# Supply_DAC.net
KiCad netlist of a schematic drawn in Altium Designer
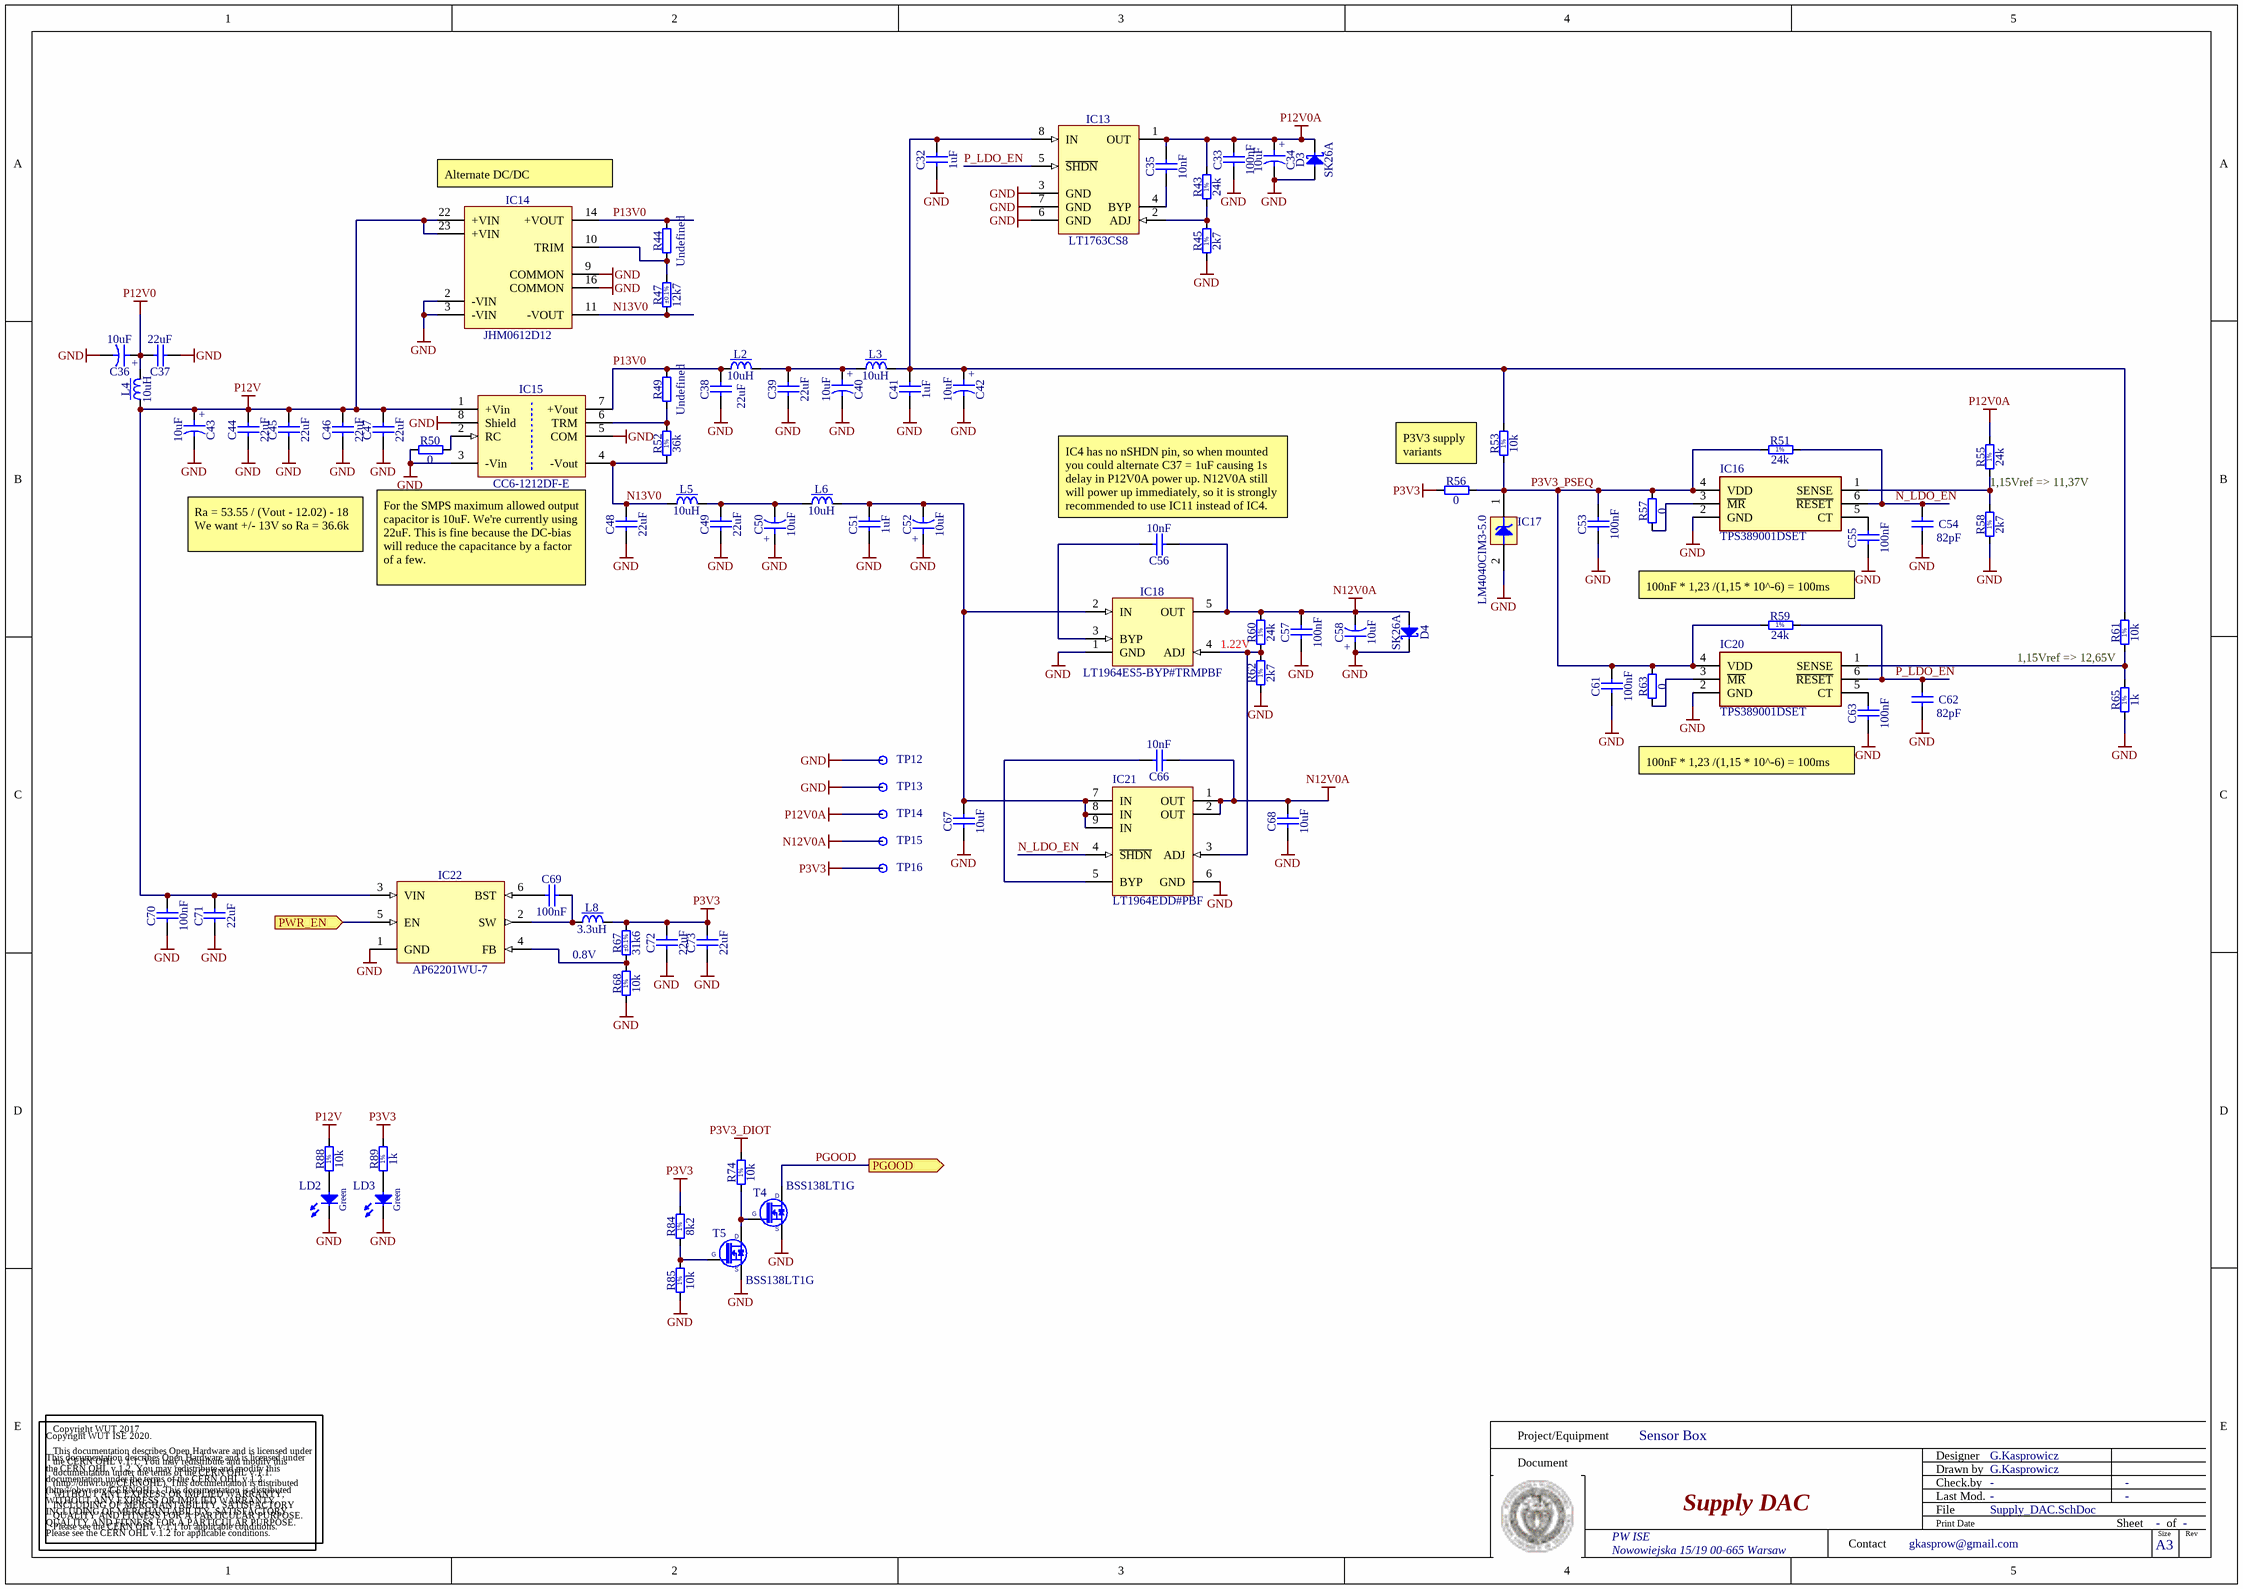
[diagram p0: Supply_DAC.SchDoc]

(export (version "E")
  (design (tool "Eeschema 10.0.6"))
  (components
    (comp (ref "C32")
      (value "1uF")
      (footprint "CAPC1608X87N")
      (description "Non-polarised capacitor")
      (fields
        (field (name "PART NUMBER") "CC0603_1UF_25V_10%_X7R")
        (field (name "VOLTAGE") "25V")
        (field (name "AUTHOR") "CERN DEM JLC")
      )
      (libsource (lib "Capacitors") (part "Capacitor - non polarized"))
    )
    (comp (ref "C33")
      (value "100nF")
      (footprint "CAPC1005X55N")
      (description "Non-polarised capacitor")
      (fields
        (field (name "PART NUMBER") "CC0402_100NF_16V_10%_X5R")
        (field (name "VOLTAGE") "16V")
        (field (name "AUTHOR") "CERN DEM JLC")
      )
      (libsource (lib "Capacitors") (part "Capacitor - non polarized"))
    )
    (comp (ref "C34")
      (value "10uF")
      (footprint "CAPMP3216X180N")
      (description "Polarised capacitor")
      (fields
        (field (name "PART NUMBER") "CTE3216-18_10UF_16V_20%_AVX_TCJ")
        (field (name "VOLTAGE") "16V")
        (field (name "AUTHOR") "CERN DEM JLC")
      )
      (libsource (lib "Capacitors") (part "Capacitor - polarized"))
    )
    (comp (ref "C35")
      (value "10nF")
      (footprint "CAPC1608X87N")
      (description "Non-polarised capacitor")
      (fields
        (field (name "PART NUMBER") "CC0603_10NF_50V_10%_X7R")
        (field (name "VOLTAGE") "50V")
        (field (name "AUTHOR") "CERN DEM JLC")
      )
      (libsource (lib "Capacitors") (part "Capacitor - non polarized"))
    )
    (comp (ref "C36")
      (value "10uF")
      (footprint "CAPMP3216X180N")
      (description "Polarised capacitor")
      (fields
        (field (name "PART NUMBER") "CTE3216-18_10UF_16V_20%_AVX_TCJ")
        (field (name "VOLTAGE") "16V")
        (field (name "AUTHOR") "CERN DEM JLC")
      )
      (libsource (lib "Capacitors") (part "Capacitor - polarized"))
    )
    (comp (ref "C37")
      (value "22uF")
      (footprint "CAPC2012X135N")
      (description "Non-polarised capacitor")
      (fields
        (field (name "PART NUMBER") "CC0805_22UF_16V_10%_X5R")
        (field (name "VOLTAGE") "16V")
        (field (name "AUTHOR") "CERN DEM JLC")
      )
      (libsource (lib "Capacitors") (part "Capacitor - non polarized"))
    )
    (comp (ref "C38")
      (value "22uF")
      (footprint "CAPC2012X135N")
      (description "Non-polarised capacitor")
      (fields
        (field (name "PART NUMBER") "CC0805_22UF_16V_10%_X5R")
        (field (name "VOLTAGE") "16V")
        (field (name "AUTHOR") "CERN DEM JLC")
      )
      (libsource (lib "Capacitors") (part "Capacitor - non polarized"))
    )
    (comp (ref "C39")
      (value "22uF")
      (footprint "CAPC2012X135N")
      (description "Non-polarised capacitor")
      (fields
        (field (name "PART NUMBER") "CC0805_22UF_16V_10%_X5R")
        (field (name "VOLTAGE") "16V")
        (field (name "AUTHOR") "CERN DEM JLC")
      )
      (libsource (lib "Capacitors") (part "Capacitor - non polarized"))
    )
    (comp (ref "C40")
      (value "10uF")
      (footprint "CAPMP3216X180N")
      (description "Polarised capacitor")
      (fields
        (field (name "PART NUMBER") "CTE3216-18_10UF_16V_20%_AVX_TCJ")
        (field (name "VOLTAGE") "16V")
        (field (name "AUTHOR") "CERN DEM JLC")
      )
      (libsource (lib "Capacitors") (part "Capacitor - polarized"))
    )
    (comp (ref "C41")
      (value "1uF")
      (footprint "CAPC1608X87N")
      (description "Non-polarised capacitor")
      (fields
        (field (name "PART NUMBER") "CC0603_1UF_25V_10%_X7R")
        (field (name "VOLTAGE") "25V")
        (field (name "AUTHOR") "CERN DEM JLC")
      )
      (libsource (lib "Capacitors") (part "Capacitor - non polarized"))
    )
    (comp (ref "C42")
      (value "10uF")
      (footprint "CAPMP3216X180N")
      (description "Polarised capacitor")
      (fields
        (field (name "PART NUMBER") "CTE3216-18_10UF_16V_20%_AVX_TCJ")
        (field (name "VOLTAGE") "16V")
        (field (name "AUTHOR") "CERN DEM JLC")
      )
      (libsource (lib "Capacitors") (part "Capacitor - polarized"))
    )
    (comp (ref "C43")
      (value "10uF")
      (footprint "CAPMP3216X180N")
      (description "Polarised capacitor")
      (fields
        (field (name "PART NUMBER") "CTE3216-18_10UF_16V_20%_AVX_TCJ")
        (field (name "VOLTAGE") "16V")
        (field (name "AUTHOR") "CERN DEM JLC")
      )
      (libsource (lib "Capacitors") (part "Capacitor - polarized"))
    )
    (comp (ref "C44")
      (value "22uF")
      (footprint "CAPC2012X135N")
      (description "Non-polarised capacitor")
      (fields
        (field (name "PART NUMBER") "CC0805_22UF_16V_10%_X5R")
        (field (name "VOLTAGE") "16V")
        (field (name "AUTHOR") "CERN DEM JLC")
      )
      (libsource (lib "Capacitors") (part "Capacitor - non polarized"))
    )
    (comp (ref "C45")
      (value "22uF")
      (footprint "CAPC2012X135N")
      (description "Non-polarised capacitor")
      (fields
        (field (name "PART NUMBER") "CC0805_22UF_16V_10%_X5R")
        (field (name "VOLTAGE") "16V")
        (field (name "AUTHOR") "CERN DEM JLC")
      )
      (libsource (lib "Capacitors") (part "Capacitor - non polarized"))
    )
    (comp (ref "C46")
      (value "22uF")
      (footprint "CAPC2012X135N")
      (description "Non-polarised capacitor")
      (fields
        (field (name "PART NUMBER") "CC0805_22UF_16V_10%_X5R")
        (field (name "VOLTAGE") "16V")
        (field (name "AUTHOR") "CERN DEM JLC")
      )
      (libsource (lib "Capacitors") (part "Capacitor - non polarized"))
    )
    (comp (ref "C47")
      (value "22uF")
      (footprint "CAPC2012X135N")
      (description "Non-polarised capacitor")
      (fields
        (field (name "PART NUMBER") "CC0805_22UF_16V_10%_X5R")
        (field (name "VOLTAGE") "16V")
        (field (name "AUTHOR") "CERN DEM JLC")
      )
      (libsource (lib "Capacitors") (part "Capacitor - non polarized"))
    )
    (comp (ref "C48")
      (value "22uF")
      (footprint "CAPC2012X135N")
      (description "Non-polarised capacitor")
      (fields
        (field (name "PART NUMBER") "CC0805_22UF_16V_10%_X5R")
        (field (name "VOLTAGE") "16V")
        (field (name "AUTHOR") "CERN DEM JLC")
      )
      (libsource (lib "Capacitors") (part "Capacitor - non polarized"))
    )
    (comp (ref "C49")
      (value "22uF")
      (footprint "CAPC2012X135N")
      (description "Non-polarised capacitor")
      (fields
        (field (name "PART NUMBER") "CC0805_22UF_16V_10%_X5R")
        (field (name "VOLTAGE") "16V")
        (field (name "AUTHOR") "CERN DEM JLC")
      )
      (libsource (lib "Capacitors") (part "Capacitor - non polarized"))
    )
    (comp (ref "C50")
      (value "10uF")
      (footprint "CAPMP3216X180N")
      (description "Polarised capacitor")
      (fields
        (field (name "PART NUMBER") "CTE3216-18_10UF_16V_20%_AVX_TCJ")
        (field (name "VOLTAGE") "16V")
        (field (name "AUTHOR") "CERN DEM JLC")
      )
      (libsource (lib "Capacitors") (part "Capacitor - polarized"))
    )
    (comp (ref "C51")
      (value "1uF")
      (footprint "CAPC1608X87N")
      (description "Non-polarised capacitor")
      (fields
        (field (name "PART NUMBER") "CC0603_1UF_25V_10%_X7R")
        (field (name "VOLTAGE") "25V")
        (field (name "AUTHOR") "CERN DEM JLC")
      )
      (libsource (lib "Capacitors") (part "Capacitor - non polarized"))
    )
    (comp (ref "C52")
      (value "10uF")
      (footprint "CAPMP3216X180N")
      (description "Polarised capacitor")
      (fields
        (field (name "PART NUMBER") "CTE3216-18_10UF_16V_20%_AVX_TCJ")
        (field (name "VOLTAGE") "16V")
        (field (name "AUTHOR") "CERN DEM JLC")
      )
      (libsource (lib "Capacitors") (part "Capacitor - polarized"))
    )
    (comp (ref "C53")
      (value "100nF")
      (footprint "CAPC1005X55N")
      (description "Non-polarised capacitor")
      (fields
        (field (name "PART NUMBER") "CC0402_100NF_16V_10%_X5R")
        (field (name "VOLTAGE") "16V")
        (field (name "AUTHOR") "CERN DEM JLC")
      )
      (libsource (lib "Capacitors") (part "Capacitor - non polarized"))
    )
    (comp (ref "C54")
      (value "82pF")
      (footprint "CAPC1608X87N")
      (description "Non-polarised capacitor")
      (fields
        (field (name "PART NUMBER") "CC0603_82PF_50V_5%_NP0")
        (field (name "VOLTAGE") "50V")
        (field (name "AUTHOR") "CERN DEM JLC")
      )
      (libsource (lib "Capacitors") (part "Capacitor - non polarized"))
    )
    (comp (ref "C55")
      (value "100nF")
      (footprint "CAPC1005X55N")
      (description "Non-polarised capacitor")
      (fields
        (field (name "PART NUMBER") "CC0402_100NF_16V_10%_X5R")
        (field (name "VOLTAGE") "16V")
        (field (name "AUTHOR") "CERN DEM JLC")
      )
      (libsource (lib "Capacitors") (part "Capacitor - non polarized"))
    )
    (comp (ref "C56")
      (value "10nF")
      (footprint "CAPC1608X87N")
      (description "Non-polarised capacitor")
      (fields
        (field (name "PART NUMBER") "CC0603_10NF_50V_10%_X7R")
        (field (name "VOLTAGE") "50V")
        (field (name "AUTHOR") "CERN DEM JLC")
      )
      (libsource (lib "Capacitors") (part "Capacitor - non polarized"))
    )
    (comp (ref "C57")
      (value "100nF")
      (footprint "CAPC1005X55N")
      (description "Non-polarised capacitor")
      (fields
        (field (name "PART NUMBER") "CC0402_100NF_16V_10%_X5R")
        (field (name "VOLTAGE") "16V")
        (field (name "AUTHOR") "CERN DEM JLC")
      )
      (libsource (lib "Capacitors") (part "Capacitor - non polarized"))
    )
    (comp (ref "C58")
      (value "10uF")
      (footprint "CAPMP3216X180N")
      (description "Polarised capacitor")
      (fields
        (field (name "PART NUMBER") "CTE3216-18_10UF_16V_20%_AVX_TCJ")
        (field (name "VOLTAGE") "16V")
        (field (name "AUTHOR") "CERN DEM JLC")
      )
      (libsource (lib "Capacitors") (part "Capacitor - polarized"))
    )
    (comp (ref "C61")
      (value "100nF")
      (footprint "CAPC1005X55N")
      (description "Non-polarised capacitor")
      (fields
        (field (name "PART NUMBER") "CC0402_100NF_16V_10%_X5R")
        (field (name "VOLTAGE") "16V")
        (field (name "AUTHOR") "CERN DEM JLC")
      )
      (libsource (lib "Capacitors") (part "Capacitor - non polarized"))
    )
    (comp (ref "C62")
      (value "82pF")
      (footprint "CAPC1608X87N")
      (description "Non-polarised capacitor")
      (fields
        (field (name "PART NUMBER") "CC0603_82PF_50V_5%_NP0")
        (field (name "VOLTAGE") "50V")
        (field (name "AUTHOR") "CERN DEM JLC")
      )
      (libsource (lib "Capacitors") (part "Capacitor - non polarized"))
    )
    (comp (ref "C63")
      (value "100nF")
      (footprint "CAPC1005X55N")
      (description "Non-polarised capacitor")
      (fields
        (field (name "PART NUMBER") "CC0402_100NF_16V_10%_X5R")
        (field (name "VOLTAGE") "16V")
        (field (name "AUTHOR") "CERN DEM JLC")
      )
      (libsource (lib "Capacitors") (part "Capacitor - non polarized"))
    )
    (comp (ref "C66")
      (value "10nF")
      (footprint "CAPC1608X87N")
      (description "Non-polarised capacitor")
      (fields
        (field (name "PART NUMBER") "CC0603_10NF_50V_10%_X7R")
        (field (name "VOLTAGE") "50V")
        (field (name "AUTHOR") "CERN DEM JLC")
      )
      (libsource (lib "Capacitors") (part "Capacitor - non polarized"))
    )
    (comp (ref "C67")
      (value "10uF")
      (footprint "CAPC1608X80N")
      (description "Non-polarised capacitor")
      (fields
        (field (name "PART NUMBER") "CC0603_10UF_16V_20%_X5R")
        (field (name "VOLTAGE") "16V")
        (field (name "AUTHOR") "CERN DEM MR")
      )
      (libsource (lib "Capacitors") (part "Capacitor - non polarized"))
    )
    (comp (ref "C68")
      (value "10uF")
      (footprint "CAPC1608X80N")
      (description "Non-polarised capacitor")
      (fields
        (field (name "PART NUMBER") "CC0603_10UF_16V_20%_X5R")
        (field (name "VOLTAGE") "16V")
        (field (name "AUTHOR") "CERN DEM MR")
      )
      (libsource (lib "Capacitors") (part "Capacitor - non polarized"))
    )
    (comp (ref "C69")
      (value "100nF")
      (footprint "CAPC1005X55N")
      (description "Non-polarised capacitor")
      (fields
        (field (name "PART NUMBER") "CC0402_100NF_16V_10%_X5R")
        (field (name "VOLTAGE") "16V")
        (field (name "AUTHOR") "CERN DEM JLC")
      )
      (libsource (lib "Capacitors") (part "Capacitor - non polarized"))
    )
    (comp (ref "C70")
      (value "100nF")
      (footprint "CAPC1005X55N")
      (description "Non-polarised capacitor")
      (fields
        (field (name "PART NUMBER") "CC0402_100NF_16V_10%_X5R")
        (field (name "VOLTAGE") "16V")
        (field (name "AUTHOR") "CERN DEM JLC")
      )
      (libsource (lib "Capacitors") (part "Capacitor - non polarized"))
    )
    (comp (ref "C71")
      (value "22uF")
      (footprint "CAPC2012X135N")
      (description "Non-polarised capacitor")
      (fields
        (field (name "PART NUMBER") "CC0805_22UF_16V_10%_X5R")
        (field (name "VOLTAGE") "16V")
        (field (name "AUTHOR") "CERN DEM JLC")
      )
      (libsource (lib "Capacitors") (part "Capacitor - non polarized"))
    )
    (comp (ref "C72")
      (value "22uF")
      (footprint "CAPC2012X135N")
      (description "Non-polarised capacitor")
      (fields
        (field (name "PART NUMBER") "CC0805_22UF_16V_10%_X5R")
        (field (name "VOLTAGE") "16V")
        (field (name "AUTHOR") "CERN DEM JLC")
      )
      (libsource (lib "Capacitors") (part "Capacitor - non polarized"))
    )
    (comp (ref "C73")
      (value "22uF")
      (footprint "CAPC2012X135N")
      (description "Non-polarised capacitor")
      (fields
        (field (name "PART NUMBER") "CC0805_22UF_16V_10%_X5R")
        (field (name "VOLTAGE") "16V")
        (field (name "AUTHOR") "CERN DEM JLC")
      )
      (libsource (lib "Capacitors") (part "Capacitor - non polarized"))
    )
    (comp (ref "D3")
      (value "SK26A")
      (footprint "DIOM5126X265N")
      (description "Schottky Diode")
      (fields
        (field (name "VOLTAGE") "60V")
        (field (name "POWER") "2A")
        (field (name "AUTHOR") "CERN DEM JMW")
      )
      (libsource (lib "ICs And Semiconductors") (part "Diode Schottky"))
    )
    (comp (ref "D4")
      (value "SK26A")
      (footprint "DIOM5126X265N")
      (description "Schottky Diode")
      (fields
        (field (name "VOLTAGE") "60V")
        (field (name "POWER") "2A")
        (field (name "AUTHOR") "CERN DEM JMW")
      )
      (libsource (lib "ICs And Semiconductors") (part "Diode Schottky"))
    )
    (comp (ref "IC13")
      (value "LT1763CS8")
      (footprint "SOIC127P600X175-8N")
      (description "1.22V to 20V 500mA, Low Noise, LDO Adjustable Micropower Regulator")
      (fields (field (name "MANUFACTURER") "LINEAR TECHNOLOGY") (field (name "AUTHOR") "CERN DEM JLC"))
      (libsource (lib "ICs And Semiconductors") (part "LT1763xS8"))
    )
    (comp (ref "IC14")
      (value "JHM0612D12")
      (footprint "DCDC_XPPOWER_JHM0X")
      (description "9-72VDC to 3.3-15VDC, Iout (max) 500mA, DC-DC Converter")
      (fields (field (name "MANUFACTURER") "XP POWER") (field (name "AUTHOR") "CERN DEM HF"))
      (libsource (lib "ICs And Semiconductors") (part "DCDC_XPPOWER_JHM0xxxD"))
    )
    (comp (ref "IC15")
      (value "CC6-1212DF-E")
      (footprint "CC6-1212DF-E")
      (description "CONV DC/DC 6W DUAL 12V +-12V PCB")
      (fields (field (name "MANUFACTURER") "TDK-Lambda Americas Inc.") (field (name "AUTHOR") "GK"))
      (libsource (lib "Regulators_SMPS") (part "DC/DC_CC6-1212DF-E"))
    )
    (comp (ref "IC16")
      (value "TPS389001DSET")
      (footprint "TPS610985DSET")
      (description "Supervisory Circuits Low-quiescent current 1% accuracy supervisor with programmable delay")
      (fields (field (name "MOUSER PART NUMBER") "595-TPS389001DSET"))
      (libsource (lib "Integrated_Library_LOADER") (part "TPS389001DSET"))
    )
    (comp (ref "IC17")
      (value "LM4040CIM3-5.0")
      (footprint "SOT95P237X112-3N")
      (description "Integrated Circuit")
      (fields (field (name "MOUSER PART NUMBER") "926-LM4040CIM3-50"))
      (libsource (lib "Integrated_Library_LOADER") (part "LM4040CIM3-5.0"))
    )
    (comp (ref "IC18")
      (value "LT1964ES5-BYP#TRMPBF")
      (footprint "SOT95P280X100-5N")
      (description "200mA, Low Noise, Low Dropout Negative Micropower Regulator")
      (fields (field (name "MANUFACTURER") "LINEAR TECHNOLOGY") (field (name "AUTHOR") "CERN DEM MR"))
      (libsource (lib "ICs And Semiconductors") (part "LT1964-BYP"))
    )
    (comp (ref "IC20")
      (value "TPS389001DSET")
      (footprint "TPS610985DSET")
      (description "Supervisory Circuits Low-quiescent current 1% accuracy supervisor with programmable delay")
      (fields (field (name "MOUSER PART NUMBER") "595-TPS389001DSET"))
      (libsource (lib "Integrated_Library_LOADER") (part "TPS389001DSET"))
    )
    (comp (ref "IC21")
      (value "LT1964EDD#PBF")
      (footprint "LT-DD-8_V")
      (fields (field (name "MANUFACTURER") "Linear Technology"))
      (libsource (lib "Altium Content Vault") (part "LT-LT1964-DD-8"))
    )
    (comp (ref "IC22")
      (value "AP62201WU-7")
      (footprint "SOT95P280X100-6N")
      (description "4.2V TO 18V INPUT, 2A LOW IQ SYNCHRONOUS BUCK CONVERTER")
      (fields
        (field (name "MANUFACTURER") "DIODES INCORPORATED")
        (field (name "MANUFACTURER PART NUMBER") "AP62201WU")
        (field (name "AUTHOR") "CERN DEM HF")
      )
      (libsource (lib "ICs And Semiconductors") (part "AP62201WU"))
    )
    (comp (ref "L2")
      (value "10uH")
      (footprint "IND_MURATA-PS_8400")
      (description "Inductor With Core")
      (fields
        (field (name "PART NUMBER") "IND_10UH_10%_MURATA-PS_8400")
        (field (name "POWER") "950mA")
        (field (name "AUTHOR") "CERN DEM JLC")
      )
      (libsource (lib "Inductors & Transformers") (part "Inductor With Magnetic core"))
    )
    (comp (ref "L3")
      (value "10uH")
      (footprint "IND_MURATA-PS_8400")
      (description "Inductor With Core")
      (fields
        (field (name "PART NUMBER") "IND_10UH_10%_MURATA-PS_8400")
        (field (name "POWER") "950mA")
        (field (name "AUTHOR") "CERN DEM JLC")
      )
      (libsource (lib "Inductors & Transformers") (part "Inductor With Magnetic core"))
    )
    (comp (ref "L4")
      (value "10uH")
      (footprint "IND_MURATA-PS_8400")
      (description "Inductor With Core")
      (fields
        (field (name "PART NUMBER") "IND_10UH_10%_MURATA-PS_8400")
        (field (name "POWER") "950mA")
        (field (name "AUTHOR") "CERN DEM JLC")
      )
      (libsource (lib "") (part "Inductor With Magnetic core_1"))
    )
    (comp (ref "L5")
      (value "10uH")
      (footprint "IND_MURATA-PS_8400")
      (description "Inductor With Core")
      (fields
        (field (name "PART NUMBER") "IND_10UH_10%_MURATA-PS_8400")
        (field (name "POWER") "950mA")
        (field (name "AUTHOR") "CERN DEM JLC")
      )
      (libsource (lib "Inductors & Transformers") (part "Inductor With Magnetic core"))
    )
    (comp (ref "L6")
      (value "10uH")
      (footprint "IND_MURATA-PS_8400")
      (description "Inductor With Core")
      (fields
        (field (name "PART NUMBER") "IND_10UH_10%_MURATA-PS_8400")
        (field (name "POWER") "950mA")
        (field (name "AUTHOR") "CERN DEM JLC")
      )
      (libsource (lib "Inductors & Transformers") (part "Inductor With Magnetic core"))
    )
    (comp (ref "L8")
      (value "3.3uH")
      (footprint "IND_WURTH_WE-TPC_4828")
      (description "Inductor With Core")
      (fields
        (field (name "PART NUMBER") "IND_3.3UH_30%_WURTH_WE-TPC_744043003")
        (field (name "POWER") "2.15A")
        (field (name "AUTHOR") "CERN DEM JLC")
      )
      (libsource (lib "Inductors & Transformers") (part "Inductor With Magnetic core"))
    )
    (comp (ref "LD2")
      (value "Green")
      (footprint "LED_KINGBRIGHT_KPH-1608CGCK")
      (description "LED Green 1C 2A")
      (fields
        (field (name "MANUFACTURER PART NUMBER") "KPH-1608CGCK")
        (field (name "PART NUMBER") "LED_KINGBRIGHT_KPH-1608CGCK")
        (field (name "AUTHOR") "CERN DEM JLC")
      )
      (libsource (lib "ICs And Semiconductors") (part "LED Green 1C 2A"))
    )
    (comp (ref "LD3")
      (value "Green")
      (footprint "LED_KINGBRIGHT_KPH-1608CGCK")
      (description "LED Green 1C 2A")
      (fields
        (field (name "MANUFACTURER PART NUMBER") "KPH-1608CGCK")
        (field (name "PART NUMBER") "LED_KINGBRIGHT_KPH-1608CGCK")
        (field (name "AUTHOR") "CERN DEM JLC")
      )
      (libsource (lib "ICs And Semiconductors") (part "LED Green 1C 2A"))
    )
    (comp (ref "R43")
      (value "24k")
      (footprint "RESC1608X55N")
      (description "Resistor - 1%")
      (fields
        (field (name "PART NUMBER") "R0603_24K_1%_0.1W_100PPM")
        (field (name "POWER") "0.1W")
        (field (name "AUTHOR") "CERN DEM JLC")
      )
      (libsource (lib "Resistors") (part "Resistor - 1%"))
    )
    (comp (ref "R44")
      (value "Undefined")
      (footprint "RESC1608X55N")
      (description "Resistor")
      (fields (field (name "PART NUMBER") "R0603_NO-VALUE") (field (name "AUTHOR") "CERN DEM JLC"))
      (libsource (lib "Resistors") (part "Resistor"))
    )
    (comp (ref "R45")
      (value "2k7")
      (footprint "RESC1608X55N")
      (description "Resistor - 1%")
      (fields
        (field (name "PART NUMBER") "R0603_2K7_1%_0.1W_100PPM")
        (field (name "POWER") "0.1W")
        (field (name "AUTHOR") "CERN DEM JLC")
      )
      (libsource (lib "Resistors") (part "Resistor - 1%"))
    )
    (comp (ref "R47")
      (value "12k7")
      (footprint "RESC1608X55N")
      (description "Resistor - 0.1%")
      (fields
        (field (name "TOLERANCE") "±0.1%")
        (field (name "PART NUMBER") "R0603_12K7_0.1%_0.063W_10PPM")
        (field (name "POWER") "0.063W")
        (field (name "AUTHOR") "CERN DEM JLC")
      )
      (libsource (lib "Resistors") (part "Resistor - 0.1%"))
    )
    (comp (ref "R49")
      (value "Undefined")
      (footprint "RESC1608X55N")
      (description "Resistor")
      (fields (field (name "PART NUMBER") "R0603_NO-VALUE") (field (name "AUTHOR") "CERN DEM JLC"))
      (libsource (lib "Resistors") (part "Resistor"))
    )
    (comp (ref "R50")
      (value "0")
      (footprint "RESC1005X40N")
      (description "Resistor")
      (fields
        (field (name "PART NUMBER") "R0402_0R_JUMPER")
        (field (name "MANUFACTURER") "GENERIC")
        (field (name "AUTHOR") "CERN DEM JLC")
      )
      (libsource (lib "Resistors") (part "Resistor"))
    )
    (comp (ref "R51")
      (value "24k")
      (footprint "RESC1608X55N")
      (description "Resistor - 1%")
      (fields
        (field (name "PART NUMBER") "R0603_24K_1%_0.1W_100PPM")
        (field (name "POWER") "0.1W")
        (field (name "AUTHOR") "CERN DEM JLC")
      )
      (libsource (lib "Resistors") (part "Resistor - 1%"))
    )
    (comp (ref "R52")
      (value "36k")
      (footprint "RESC1608X55N")
      (description "Resistor - 1%")
      (fields
        (field (name "PART NUMBER") "R0603_36K_1%_0.1W_100PPM")
        (field (name "POWER") "0.1W")
        (field (name "AUTHOR") "CERN DEM JLC")
      )
      (libsource (lib "Resistors") (part "Resistor - 1%"))
    )
    (comp (ref "R53")
      (value "10k")
      (footprint "RESC1005X40N")
      (description "Resistor - 1%")
      (fields
        (field (name "PART NUMBER") "R0402_10K_1%_0.0625W_100PPM")
        (field (name "POWER") "0.0625W")
        (field (name "AUTHOR") "CERN DEM JLC")
      )
      (libsource (lib "Resistors") (part "Resistor - 1%"))
    )
    (comp (ref "R55")
      (value "24k")
      (footprint "RESC1608X55N")
      (description "Resistor - 1%")
      (fields
        (field (name "PART NUMBER") "R0603_24K_1%_0.1W_100PPM")
        (field (name "POWER") "0.1W")
        (field (name "AUTHOR") "CERN DEM JLC")
      )
      (libsource (lib "Resistors") (part "Resistor - 1%"))
    )
    (comp (ref "R56")
      (value "0")
      (footprint "RESC1005X40N")
      (description "Resistor")
      (fields
        (field (name "PART NUMBER") "R0402_0R_JUMPER")
        (field (name "MANUFACTURER") "GENERIC")
        (field (name "AUTHOR") "CERN DEM JLC")
      )
      (libsource (lib "Resistors") (part "Resistor"))
    )
    (comp (ref "R57")
      (value "0")
      (footprint "RESC1005X40N")
      (description "Resistor")
      (fields
        (field (name "PART NUMBER") "R0402_0R_JUMPER")
        (field (name "MANUFACTURER") "GENERIC")
        (field (name "AUTHOR") "CERN DEM JLC")
      )
      (libsource (lib "Resistors") (part "Resistor"))
    )
    (comp (ref "R58")
      (value "2k7")
      (footprint "RESC1608X55N")
      (description "Resistor - 1%")
      (fields
        (field (name "PART NUMBER") "R0603_2K7_1%_0.1W_100PPM")
        (field (name "POWER") "0.1W")
        (field (name "AUTHOR") "CERN DEM JLC")
      )
      (libsource (lib "Resistors") (part "Resistor - 1%"))
    )
    (comp (ref "R59")
      (value "24k")
      (footprint "RESC1608X55N")
      (description "Resistor - 1%")
      (fields
        (field (name "PART NUMBER") "R0603_24K_1%_0.1W_100PPM")
        (field (name "POWER") "0.1W")
        (field (name "AUTHOR") "CERN DEM JLC")
      )
      (libsource (lib "Resistors") (part "Resistor - 1%"))
    )
    (comp (ref "R60")
      (value "24k")
      (footprint "RESC1608X55N")
      (description "Resistor - 1%")
      (fields
        (field (name "PART NUMBER") "R0603_24K_1%_0.1W_100PPM")
        (field (name "POWER") "0.1W")
        (field (name "AUTHOR") "CERN DEM JLC")
      )
      (libsource (lib "Resistors") (part "Resistor - 1%"))
    )
    (comp (ref "R61")
      (value "10k")
      (footprint "RESC1005X40N")
      (description "Resistor - 1%")
      (fields
        (field (name "PART NUMBER") "R0402_10K_1%_0.0625W_100PPM")
        (field (name "POWER") "0.0625W")
        (field (name "AUTHOR") "CERN DEM JLC")
      )
      (libsource (lib "Resistors") (part "Resistor - 1%"))
    )
    (comp (ref "R62")
      (value "2k7")
      (footprint "RESC1608X55N")
      (description "Resistor - 1%")
      (fields
        (field (name "PART NUMBER") "R0603_2K7_1%_0.1W_100PPM")
        (field (name "POWER") "0.1W")
        (field (name "AUTHOR") "CERN DEM JLC")
      )
      (libsource (lib "Resistors") (part "Resistor - 1%"))
    )
    (comp (ref "R63")
      (value "0")
      (footprint "RESC1005X40N")
      (description "Resistor")
      (fields
        (field (name "PART NUMBER") "R0402_0R_JUMPER")
        (field (name "MANUFACTURER") "GENERIC")
        (field (name "AUTHOR") "CERN DEM JLC")
      )
      (libsource (lib "Resistors") (part "Resistor"))
    )
    (comp (ref "R65")
      (value "1k")
      (footprint "RESC1608X55N")
      (description "Resistor - 1%")
      (fields
        (field (name "PART NUMBER") "R0603_1K_1%_0.1W_100PPM")
        (field (name "POWER") "0.1W")
        (field (name "AUTHOR") "CERN DEM JLC")
      )
      (libsource (lib "Resistors") (part "Resistor - 1%"))
    )
    (comp (ref "R67")
      (value "31k6")
      (footprint "RESC1005X35N")
      (description "Resistor - 0.1%")
      (fields
        (field (name "TOLERANCE") "±0.1%")
        (field (name "PART NUMBER") "R0402_31K6_0.1%_0.063W_25PPM_YAGEO_RT")
        (field (name "POWER") "0.063W")
        (field (name "AUTHOR") "CERN DEM BC")
      )
      (libsource (lib "Resistors") (part "Resistor - 0.1%"))
    )
    (comp (ref "R68")
      (value "10k")
      (footprint "RESC1005X40N")
      (description "Resistor - 1%")
      (fields
        (field (name "PART NUMBER") "R0402_10K_1%_0.0625W_100PPM")
        (field (name "POWER") "0.0625W")
        (field (name "AUTHOR") "CERN DEM JLC")
      )
      (libsource (lib "Resistors") (part "Resistor - 1%"))
    )
    (comp (ref "R74")
      (value "10k")
      (footprint "RESC1005X40N")
      (description "Resistor - 1%")
      (fields
        (field (name "PART NUMBER") "R0402_10K_1%_0.0625W_100PPM")
        (field (name "POWER") "0.0625W")
        (field (name "AUTHOR") "CERN DEM JLC")
      )
      (libsource (lib "Resistors") (part "Resistor - 1%"))
    )
    (comp (ref "R84")
      (value "8k2")
      (footprint "RESC1005X40N")
      (description "Resistor - 1%")
      (fields
        (field (name "PART NUMBER") "R0402_8K2_1%_0.0625W_100PPM")
        (field (name "POWER") "0.0625W")
        (field (name "AUTHOR") "CERN DEM JLC")
      )
      (libsource (lib "Resistors") (part "Resistor - 1%"))
    )
    (comp (ref "R85")
      (value "10k")
      (footprint "RESC1005X40N")
      (description "Resistor - 1%")
      (fields
        (field (name "PART NUMBER") "R0402_10K_1%_0.0625W_100PPM")
        (field (name "POWER") "0.0625W")
        (field (name "AUTHOR") "CERN DEM JLC")
      )
      (libsource (lib "Resistors") (part "Resistor - 1%"))
    )
    (comp (ref "R88")
      (value "10k")
      (footprint "RESC1005X40N")
      (description "Resistor - 1%")
      (fields
        (field (name "PART NUMBER") "R0402_10K_1%_0.0625W_100PPM")
        (field (name "POWER") "0.0625W")
        (field (name "AUTHOR") "CERN DEM JLC")
      )
      (libsource (lib "Resistors") (part "Resistor - 1%"))
    )
    (comp (ref "R89")
      (value "1k")
      (footprint "RESC1005X40N")
      (description "Resistor - 1%")
      (fields
        (field (name "PART NUMBER") "R0402_1K_1%_0.0625W_100PPM")
        (field (name "POWER") "0.0625W")
        (field (name "AUTHOR") "CERN DEM JLC")
      )
      (libsource (lib "Resistors") (part "Resistor - 1%"))
    )
    (comp (ref "T4")
      (value "BSS138LT1G")
      (footprint "SOT95P240X110-3N")
      (description "N-CHANNEL MOSFET WITH DIODE")
      (fields (field (name "MANUFACTURER") "ON SEMICONDUCTOR") (field (name "AUTHOR") "CERN DEM JLC"))
      (libsource (lib "ICs And Semiconductors") (part "N-MOSFET-D 1G 2S 3D"))
    )
    (comp (ref "T5")
      (value "BSS138LT1G")
      (footprint "SOT95P240X110-3N")
      (description "N-CHANNEL MOSFET WITH DIODE")
      (fields (field (name "MANUFACTURER") "ON SEMICONDUCTOR") (field (name "AUTHOR") "CERN DEM JLC"))
      (libsource (lib "ICs And Semiconductors") (part "N-MOSFET-D 1G 2S 3D"))
    )
    (comp (ref "TP12")
      (value "Test Point")
      (footprint "TPS127")
      (fields (field (name "PART NUMBER") "SMD_PAD_1.27X1.27MM") (field (name "AUTHOR") "CERN DEM JLC"))
      (libsource (lib "Eletro-mechanical") (part "Test Point"))
    )
    (comp (ref "TP13")
      (value "Test Point")
      (footprint "TPS127")
      (fields (field (name "PART NUMBER") "SMD_PAD_1.27X1.27MM") (field (name "AUTHOR") "CERN DEM JLC"))
      (libsource (lib "Eletro-mechanical") (part "Test Point"))
    )
    (comp (ref "TP14")
      (value "Test Point")
      (footprint "TPS127")
      (fields (field (name "PART NUMBER") "SMD_PAD_1.27X1.27MM") (field (name "AUTHOR") "CERN DEM JLC"))
      (libsource (lib "Eletro-mechanical") (part "Test Point"))
    )
    (comp (ref "TP15")
      (value "Test Point")
      (footprint "TPS127")
      (fields (field (name "PART NUMBER") "SMD_PAD_1.27X1.27MM") (field (name "AUTHOR") "CERN DEM JLC"))
      (libsource (lib "Eletro-mechanical") (part "Test Point"))
    )
    (comp (ref "TP16")
      (value "Test Point")
      (footprint "TPS127")
      (fields (field (name "PART NUMBER") "SMD_PAD_1.27X1.27MM") (field (name "AUTHOR") "CERN DEM JLC"))
      (libsource (lib "Eletro-mechanical") (part "Test Point"))
    )
  )
  (nets
    (net (code "1") (name "/N13V0") (class "Default")
      (node (ref "C48") (pin "2") (pinfunction "2_2") (pintype "passive"))
      (node (ref "IC14") (pin "11") (pinfunction "-VOUT_11") (pintype "power_in"))
      (node (ref "IC15") (pin "4") (pinfunction "-Vout_4") (pintype "power_in"))
      (node (ref "L5") (pin "1") (pinfunction "1_1") (pintype "passive"))
      (node (ref "R47") (pin "1") (pinfunction "1_1") (pintype "passive"))
      (node (ref "R52") (pin "1") (pinfunction "1_1") (pintype "passive"))
    )
    (net (code "2") (name "/N_LDO_EN") (class "Default")
      (node (ref "C54") (pin "2") (pinfunction "2_2") (pintype "passive"))
      (node (ref "IC16") (pin "6") (pinfunction "~{RESET}_6") (pintype "passive"))
      (node (ref "IC21") (pin "4") (pinfunction "~{SHDN}_4") (pintype "input"))
      (node (ref "R51") (pin "2") (pinfunction "2_2") (pintype "passive"))
    )
    (net (code "3") (name "/P3V3_PSEQ") (class "Default")
      (node (ref "C53") (pin "2") (pinfunction "2_2") (pintype "passive"))
      (node (ref "C61") (pin "2") (pinfunction "2_2") (pintype "passive"))
      (node (ref "IC16") (pin "4") (pinfunction "VDD_4") (pintype "passive"))
      (node (ref "IC17") (pin "1") (pinfunction "C_1") (pintype "passive"))
      (node (ref "IC20") (pin "4") (pinfunction "VDD_4") (pintype "passive"))
      (node (ref "R51") (pin "1") (pinfunction "1_1") (pintype "passive"))
      (node (ref "R53") (pin "1") (pinfunction "1_1") (pintype "passive"))
      (node (ref "R56") (pin "2") (pinfunction "2_2") (pintype "passive"))
      (node (ref "R57") (pin "2") (pinfunction "2_2") (pintype "passive"))
      (node (ref "R59") (pin "1") (pinfunction "1_1") (pintype "passive"))
      (node (ref "R63") (pin "2") (pinfunction "2_2") (pintype "passive"))
    )
    (net (code "4") (name "/P13V0") (class "Default")
      (node (ref "C38") (pin "2") (pinfunction "2_2") (pintype "passive"))
      (node (ref "IC14") (pin "14") (pinfunction "+VOUT_14") (pintype "power_in"))
      (node (ref "IC15") (pin "7") (pinfunction "+Vout_7") (pintype "power_in"))
      (node (ref "L2") (pin "1") (pinfunction "1_1") (pintype "passive"))
      (node (ref "R44") (pin "2") (pinfunction "2_2") (pintype "passive"))
      (node (ref "R49") (pin "2") (pinfunction "2_2") (pintype "passive"))
    )
    (net (code "5") (name "/PGOOD") (class "Default")
      (node (ref "T4") (pin "3") (pinfunction "D_3") (pintype "passive"))
    )
    (net (code "6") (name "/PWR_EN") (class "Default")
      (node (ref "IC22") (pin "5") (pinfunction "EN_5") (pintype "input"))
    )
    (net (code "7") (name "/P_LDO_EN") (class "Default")
      (node (ref "C62") (pin "2") (pinfunction "2_2") (pintype "passive"))
      (node (ref "IC13") (pin "5") (pinfunction "~{SHDN}_5") (pintype "input"))
      (node (ref "IC20") (pin "6") (pinfunction "~{RESET}_6") (pintype "passive"))
      (node (ref "R59") (pin "2") (pinfunction "2_2") (pintype "passive"))
    )
    (net (code "8") (name "GND") (class "Default")
      (node (ref "C32") (pin "1") (pinfunction "1_1") (pintype "passive"))
      (node (ref "C33") (pin "1") (pinfunction "1_1") (pintype "passive"))
      (node (ref "C34") (pin "2") (pinfunction "2_2") (pintype "passive"))
      (node (ref "C36") (pin "2") (pinfunction "2_2") (pintype "passive"))
      (node (ref "C37") (pin "1") (pinfunction "1_1") (pintype "passive"))
      (node (ref "C38") (pin "1") (pinfunction "1_1") (pintype "passive"))
      (node (ref "C39") (pin "1") (pinfunction "1_1") (pintype "passive"))
      (node (ref "C40") (pin "2") (pinfunction "2_2") (pintype "passive"))
      (node (ref "C41") (pin "1") (pinfunction "1_1") (pintype "passive"))
      (node (ref "C42") (pin "2") (pinfunction "2_2") (pintype "passive"))
      (node (ref "C43") (pin "2") (pinfunction "2_2") (pintype "passive"))
      (node (ref "C44") (pin "1") (pinfunction "1_1") (pintype "passive"))
      (node (ref "C45") (pin "1") (pinfunction "1_1") (pintype "passive"))
      (node (ref "C46") (pin "1") (pinfunction "1_1") (pintype "passive"))
      (node (ref "C47") (pin "1") (pinfunction "1_1") (pintype "passive"))
      (node (ref "C48") (pin "1") (pinfunction "1_1") (pintype "passive"))
      (node (ref "C49") (pin "1") (pinfunction "1_1") (pintype "passive"))
      (node (ref "C50") (pin "1") (pinfunction "1_1") (pintype "passive"))
      (node (ref "C51") (pin "1") (pinfunction "1_1") (pintype "passive"))
      (node (ref "C52") (pin "1") (pinfunction "1_1") (pintype "passive"))
      (node (ref "C53") (pin "1") (pinfunction "1_1") (pintype "passive"))
      (node (ref "C54") (pin "1") (pinfunction "1_1") (pintype "passive"))
      (node (ref "C55") (pin "1") (pinfunction "1_1") (pintype "passive"))
      (node (ref "C57") (pin "1") (pinfunction "1_1") (pintype "passive"))
      (node (ref "C58") (pin "1") (pinfunction "1_1") (pintype "passive"))
      (node (ref "C61") (pin "1") (pinfunction "1_1") (pintype "passive"))
      (node (ref "C62") (pin "1") (pinfunction "1_1") (pintype "passive"))
      (node (ref "C63") (pin "1") (pinfunction "1_1") (pintype "passive"))
      (node (ref "C67") (pin "1") (pinfunction "1_1") (pintype "passive"))
      (node (ref "C68") (pin "1") (pinfunction "1_1") (pintype "passive"))
      (node (ref "C70") (pin "1") (pinfunction "1_1") (pintype "passive"))
      (node (ref "C71") (pin "1") (pinfunction "1_1") (pintype "passive"))
      (node (ref "C72") (pin "1") (pinfunction "1_1") (pintype "passive"))
      (node (ref "C73") (pin "1") (pinfunction "1_1") (pintype "passive"))
      (node (ref "D3") (pin "2") (pinfunction "A_2") (pintype "passive"))
      (node (ref "D4") (pin "1") (pinfunction "C_1") (pintype "passive"))
      (node (ref "IC13") (pin "3") (pinfunction "GND_3") (pintype "power_in"))
      (node (ref "IC13") (pin "6") (pinfunction "GND_6") (pintype "power_in"))
      (node (ref "IC13") (pin "7") (pinfunction "GND_7") (pintype "power_in"))
      (node (ref "IC14") (pin "16") (pinfunction "COMMON_16") (pintype "power_in"))
      (node (ref "IC14") (pin "2") (pinfunction "-VIN_2") (pintype "power_in"))
      (node (ref "IC14") (pin "3") (pinfunction "-VIN_3") (pintype "power_in"))
      (node (ref "IC14") (pin "9") (pinfunction "COMMON_9") (pintype "power_in"))
      (node (ref "IC15") (pin "3") (pinfunction "-Vin_3") (pintype "power_in"))
      (node (ref "IC15") (pin "5") (pinfunction "COM_5") (pintype "power_in"))
      (node (ref "IC15") (pin "8") (pinfunction "Shield_8") (pintype "power_in"))
      (node (ref "IC16") (pin "2") (pinfunction "GND_2") (pintype "passive"))
      (node (ref "IC17") (pin "2") (pinfunction "A_2") (pintype "passive"))
      (node (ref "IC18") (pin "1") (pinfunction "GND_1") (pintype "power_in"))
      (node (ref "IC20") (pin "2") (pinfunction "GND_2") (pintype "passive"))
      (node (ref "IC21") (pin "6") (pinfunction "GND_6") (pintype "power_in"))
      (node (ref "IC22") (pin "1") (pinfunction "GND_1") (pintype "power_in"))
      (node (ref "LD2") (pin "1") (pinfunction "C_1") (pintype "passive"))
      (node (ref "LD3") (pin "1") (pinfunction "C_1") (pintype "passive"))
      (node (ref "R45") (pin "1") (pinfunction "1_1") (pintype "passive"))
      (node (ref "R50") (pin "1") (pinfunction "1_1") (pintype "passive"))
      (node (ref "R58") (pin "1") (pinfunction "1_1") (pintype "passive"))
      (node (ref "R62") (pin "1") (pinfunction "1_1") (pintype "passive"))
      (node (ref "R65") (pin "1") (pinfunction "1_1") (pintype "passive"))
      (node (ref "R68") (pin "1") (pinfunction "1_1") (pintype "passive"))
      (node (ref "R85") (pin "1") (pinfunction "1_1") (pintype "passive"))
      (node (ref "T4") (pin "2") (pinfunction "S_2") (pintype "passive"))
      (node (ref "T5") (pin "2") (pinfunction "S_2") (pintype "passive"))
      (node (ref "TP12") (pin "1") (pinfunction "1_1") (pintype "bidirectional"))
      (node (ref "TP13") (pin "1") (pinfunction "1_1") (pintype "bidirectional"))
    )
    (net (code "9") (name "N12V0A") (class "Default")
      (node (ref "C56") (pin "1") (pinfunction "1_1") (pintype "passive"))
      (node (ref "C57") (pin "2") (pinfunction "2_2") (pintype "passive"))
      (node (ref "C58") (pin "2") (pinfunction "2_2") (pintype "passive"))
      (node (ref "C66") (pin "1") (pinfunction "1_1") (pintype "passive"))
      (node (ref "C68") (pin "2") (pinfunction "2_2") (pintype "passive"))
      (node (ref "D4") (pin "2") (pinfunction "A_2") (pintype "passive"))
      (node (ref "IC18") (pin "5") (pinfunction "OUT_5") (pintype "power_in"))
      (node (ref "IC21") (pin "1") (pinfunction "OUT_1") (pintype "power_in"))
      (node (ref "IC21") (pin "2") (pinfunction "OUT_2") (pintype "power_in"))
      (node (ref "R60") (pin "2") (pinfunction "2_2") (pintype "passive"))
      (node (ref "TP15") (pin "1") (pinfunction "1_1") (pintype "bidirectional"))
    )
    (net (code "10") (name "Net-(C39-Pad2)") (class "Default")
      (node (ref "C39") (pin "2") (pinfunction "2_2") (pintype "passive"))
      (node (ref "C40") (pin "1") (pinfunction "1_1") (pintype "passive"))
      (node (ref "L2") (pin "2") (pinfunction "2_2") (pintype "passive"))
      (node (ref "L3") (pin "1") (pinfunction "1_1") (pintype "passive"))
    )
    (net (code "11") (name "Net-(C49-Pad2)") (class "Default")
      (node (ref "C49") (pin "2") (pinfunction "2_2") (pintype "passive"))
      (node (ref "C50") (pin "2") (pinfunction "2_2") (pintype "passive"))
      (node (ref "L5") (pin "2") (pinfunction "2_2") (pintype "passive"))
      (node (ref "L6") (pin "1") (pinfunction "1_1") (pintype "passive"))
    )
    (net (code "12") (name "Net-(IC13-ADJ)") (class "Default")
      (node (ref "IC13") (pin "2") (pinfunction "ADJ_2") (pintype "input"))
      (node (ref "R43") (pin "1") (pinfunction "1_1") (pintype "passive"))
      (node (ref "R45") (pin "2") (pinfunction "2_2") (pintype "passive"))
    )
    (net (code "13") (name "Net-(IC13-BYP)") (class "Default")
      (node (ref "C35") (pin "1") (pinfunction "1_1") (pintype "passive"))
      (node (ref "IC13") (pin "4") (pinfunction "BYP_4") (pintype "passive"))
    )
    (net (code "14") (name "Net-(IC13-IN)") (class "Default")
      (node (ref "C32") (pin "2") (pinfunction "2_2") (pintype "passive"))
      (node (ref "C41") (pin "2") (pinfunction "2_2") (pintype "passive"))
      (node (ref "C42") (pin "1") (pinfunction "1_1") (pintype "passive"))
      (node (ref "IC13") (pin "8") (pinfunction "IN_8") (pintype "input"))
      (node (ref "L3") (pin "2") (pinfunction "2_2") (pintype "passive"))
      (node (ref "R53") (pin "2") (pinfunction "2_2") (pintype "passive"))
      (node (ref "R61") (pin "2") (pinfunction "2_2") (pintype "passive"))
    )
    (net (code "15") (name "Net-(IC14-TRIM)") (class "Default")
      (node (ref "IC14") (pin "10") (pinfunction "TRIM_10") (pintype "power_in"))
      (node (ref "R44") (pin "1") (pinfunction "1_1") (pintype "passive"))
      (node (ref "R47") (pin "2") (pinfunction "2_2") (pintype "passive"))
    )
    (net (code "16") (name "Net-(IC15-RC)") (class "Default")
      (node (ref "IC15") (pin "2") (pinfunction "RC_2") (pintype "input"))
      (node (ref "R50") (pin "2") (pinfunction "2_2") (pintype "passive"))
    )
    (net (code "17") (name "Net-(IC15-TRM)") (class "Default")
      (node (ref "IC15") (pin "6") (pinfunction "TRM_6") (pintype "power_in"))
      (node (ref "R49") (pin "1") (pinfunction "1_1") (pintype "passive"))
      (node (ref "R52") (pin "2") (pinfunction "2_2") (pintype "passive"))
    )
    (net (code "18") (name "Net-(IC16-CT)") (class "Default")
      (node (ref "C55") (pin "2") (pinfunction "2_2") (pintype "passive"))
      (node (ref "IC16") (pin "5") (pinfunction "CT_5") (pintype "passive"))
    )
    (net (code "19") (name "Net-(IC16-SENSE)") (class "Default")
      (node (ref "IC16") (pin "1") (pinfunction "SENSE_1") (pintype "passive"))
      (node (ref "R55") (pin "1") (pinfunction "1_1") (pintype "passive"))
      (node (ref "R58") (pin "2") (pinfunction "2_2") (pintype "passive"))
    )
    (net (code "20") (name "Net-(IC16-~{MR})") (class "Default")
      (node (ref "IC16") (pin "3") (pinfunction "~{MR}_3") (pintype "passive"))
      (node (ref "R57") (pin "1") (pinfunction "1_1") (pintype "passive"))
    )
    (net (code "21") (name "Net-(IC18-ADJ)") (class "Default")
      (node (ref "IC18") (pin "4") (pinfunction "ADJ_4") (pintype "input"))
      (node (ref "IC21") (pin "3") (pinfunction "ADJ_3") (pintype "input"))
      (node (ref "R60") (pin "1") (pinfunction "1_1") (pintype "passive"))
      (node (ref "R62") (pin "2") (pinfunction "2_2") (pintype "passive"))
    )
    (net (code "22") (name "Net-(IC18-BYP)") (class "Default")
      (node (ref "C56") (pin "2") (pinfunction "2_2") (pintype "passive"))
      (node (ref "IC18") (pin "3") (pinfunction "BYP_3") (pintype "input"))
    )
    (net (code "23") (name "Net-(IC18-IN)") (class "Default")
      (node (ref "C51") (pin "2") (pinfunction "2_2") (pintype "passive"))
      (node (ref "C52") (pin "2") (pinfunction "2_2") (pintype "passive"))
      (node (ref "C67") (pin "2") (pinfunction "2_2") (pintype "passive"))
      (node (ref "IC18") (pin "2") (pinfunction "IN_2") (pintype "input"))
      (node (ref "IC21") (pin "7") (pinfunction "IN_7") (pintype "power_in"))
      (node (ref "IC21") (pin "8") (pinfunction "IN_8") (pintype "power_in"))
      (node (ref "IC21") (pin "9") (pinfunction "IN_9") (pintype "power_in"))
      (node (ref "L6") (pin "2") (pinfunction "2_2") (pintype "passive"))
    )
    (net (code "24") (name "Net-(IC20-CT)") (class "Default")
      (node (ref "C63") (pin "2") (pinfunction "2_2") (pintype "passive"))
      (node (ref "IC20") (pin "5") (pinfunction "CT_5") (pintype "passive"))
    )
    (net (code "25") (name "Net-(IC20-SENSE)") (class "Default")
      (node (ref "IC20") (pin "1") (pinfunction "SENSE_1") (pintype "passive"))
      (node (ref "R61") (pin "1") (pinfunction "1_1") (pintype "passive"))
      (node (ref "R65") (pin "2") (pinfunction "2_2") (pintype "passive"))
    )
    (net (code "26") (name "Net-(IC20-~{MR})") (class "Default")
      (node (ref "IC20") (pin "3") (pinfunction "~{MR}_3") (pintype "passive"))
      (node (ref "R63") (pin "1") (pinfunction "1_1") (pintype "passive"))
    )
    (net (code "27") (name "Net-(IC21-BYP)") (class "Default")
      (node (ref "C66") (pin "2") (pinfunction "2_2") (pintype "passive"))
      (node (ref "IC21") (pin "5") (pinfunction "BYP_5") (pintype "passive"))
    )
    (net (code "28") (name "Net-(IC22-BST)") (class "Default")
      (node (ref "C69") (pin "1") (pinfunction "1_1") (pintype "passive"))
      (node (ref "IC22") (pin "6") (pinfunction "BST_6") (pintype "input"))
    )
    (net (code "29") (name "Net-(IC22-FB)") (class "Default")
      (node (ref "IC22") (pin "4") (pinfunction "FB_4") (pintype "input"))
      (node (ref "R67") (pin "1") (pinfunction "1_1") (pintype "passive"))
      (node (ref "R68") (pin "2") (pinfunction "2_2") (pintype "passive"))
    )
    (net (code "30") (name "Net-(IC22-SW)") (class "Default")
      (node (ref "C69") (pin "2") (pinfunction "2_2") (pintype "passive"))
      (node (ref "IC22") (pin "2") (pinfunction "SW_2") (pintype "output"))
      (node (ref "L8") (pin "1") (pinfunction "1_1") (pintype "passive"))
    )
    (net (code "31") (name "Net-(LD2-A)") (class "Default")
      (node (ref "LD2") (pin "2") (pinfunction "A_2") (pintype "passive"))
      (node (ref "R88") (pin "1") (pinfunction "1_1") (pintype "passive"))
    )
    (net (code "32") (name "Net-(LD3-A)") (class "Default")
      (node (ref "LD3") (pin "2") (pinfunction "A_2") (pintype "passive"))
      (node (ref "R89") (pin "1") (pinfunction "1_1") (pintype "passive"))
    )
    (net (code "33") (name "Net-(T4-G)") (class "Default")
      (node (ref "R74") (pin "1") (pinfunction "1_1") (pintype "passive"))
      (node (ref "T4") (pin "1") (pinfunction "G_1") (pintype "passive"))
      (node (ref "T5") (pin "3") (pinfunction "D_3") (pintype "passive"))
    )
    (net (code "34") (name "Net-(T5-G)") (class "Default")
      (node (ref "R84") (pin "1") (pinfunction "1_1") (pintype "passive"))
      (node (ref "R85") (pin "2") (pinfunction "2_2") (pintype "passive"))
      (node (ref "T5") (pin "1") (pinfunction "G_1") (pintype "passive"))
    )
    (net (code "35") (name "P3V3") (class "Default")
      (node (ref "C72") (pin "2") (pinfunction "2_2") (pintype "passive"))
      (node (ref "C73") (pin "2") (pinfunction "2_2") (pintype "passive"))
      (node (ref "L8") (pin "2") (pinfunction "2_2") (pintype "passive"))
      (node (ref "R56") (pin "1") (pinfunction "1_1") (pintype "passive"))
      (node (ref "R67") (pin "2") (pinfunction "2_2") (pintype "passive"))
      (node (ref "R84") (pin "2") (pinfunction "2_2") (pintype "passive"))
      (node (ref "R89") (pin "2") (pinfunction "2_2") (pintype "passive"))
      (node (ref "TP16") (pin "1") (pinfunction "1_1") (pintype "bidirectional"))
    )
    (net (code "36") (name "P3V3_DIOT") (class "Default")
      (node (ref "R74") (pin "2") (pinfunction "2_2") (pintype "passive"))
    )
    (net (code "37") (name "P12V") (class "Default")
      (node (ref "C43") (pin "1") (pinfunction "1_1") (pintype "passive"))
      (node (ref "C44") (pin "2") (pinfunction "2_2") (pintype "passive"))
      (node (ref "C45") (pin "2") (pinfunction "2_2") (pintype "passive"))
      (node (ref "C46") (pin "2") (pinfunction "2_2") (pintype "passive"))
      (node (ref "C47") (pin "2") (pinfunction "2_2") (pintype "passive"))
      (node (ref "C70") (pin "2") (pinfunction "2_2") (pintype "passive"))
      (node (ref "C71") (pin "2") (pinfunction "2_2") (pintype "passive"))
      (node (ref "IC14") (pin "22") (pinfunction "+VIN_22") (pintype "power_in"))
      (node (ref "IC14") (pin "23") (pinfunction "+VIN_23") (pintype "power_in"))
      (node (ref "IC15") (pin "1") (pinfunction "+Vin_1") (pintype "power_in"))
      (node (ref "IC22") (pin "3") (pinfunction "VIN_3") (pintype "input"))
      (node (ref "L4") (pin "1") (pinfunction "1_1") (pintype "passive"))
      (node (ref "R88") (pin "2") (pinfunction "2_2") (pintype "passive"))
    )
    (net (code "38") (name "P12V0") (class "Default")
      (node (ref "C36") (pin "1") (pinfunction "1_1") (pintype "passive"))
      (node (ref "C37") (pin "2") (pinfunction "2_2") (pintype "passive"))
      (node (ref "L4") (pin "2") (pinfunction "2_2") (pintype "passive"))
    )
    (net (code "39") (name "P12V0A") (class "Default")
      (node (ref "C33") (pin "2") (pinfunction "2_2") (pintype "passive"))
      (node (ref "C34") (pin "1") (pinfunction "1_1") (pintype "passive"))
      (node (ref "C35") (pin "2") (pinfunction "2_2") (pintype "passive"))
      (node (ref "D3") (pin "1") (pinfunction "C_1") (pintype "passive"))
      (node (ref "IC13") (pin "1") (pinfunction "OUT_1") (pintype "power_in"))
      (node (ref "R43") (pin "2") (pinfunction "2_2") (pintype "passive"))
      (node (ref "R55") (pin "2") (pinfunction "2_2") (pintype "passive"))
      (node (ref "TP14") (pin "1") (pinfunction "1_1") (pintype "bidirectional"))
    )
  )
)
